# Schematics_MedidorDeTensionAC.net
KiCad netlist of a schematic drawn in EAGLE
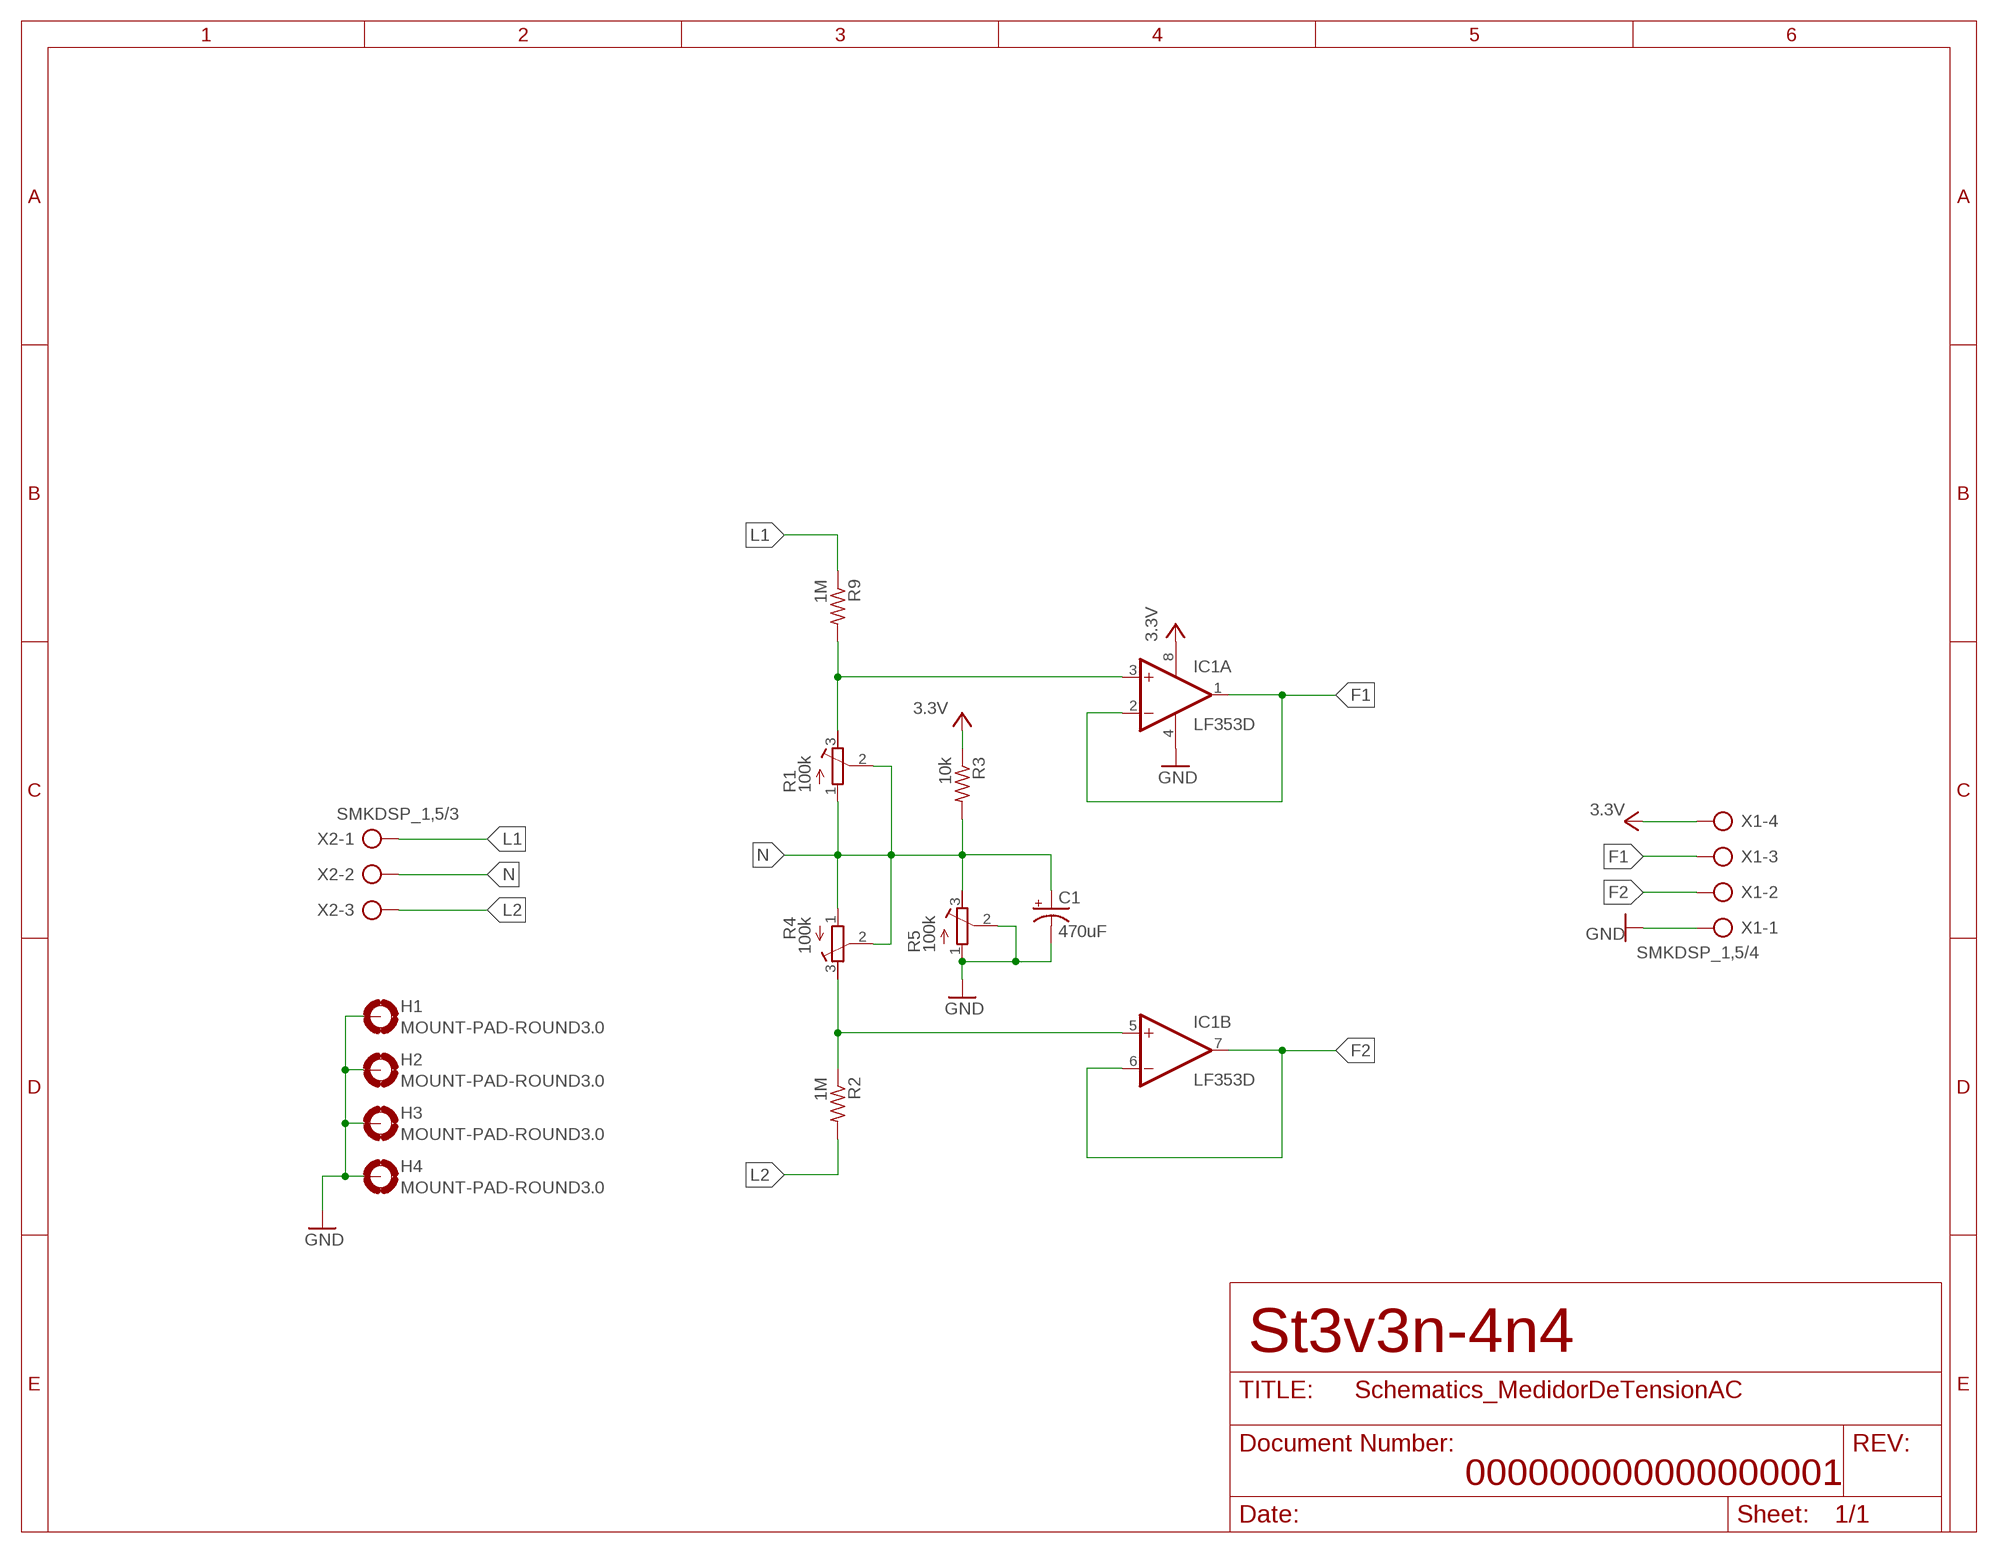
[diagram p0: schematic, sheet 1]

(export (version "E")
  (design (tool "Eeschema 10.0.6"))
  (components
    (comp (ref "C1")
      (value "470uF")
      (footprint "eagle-import:E3,5-8")
      (libsource (lib "eagle-import") (part "CPOL-USE3.5-8"))
    )
    (comp (ref "H1")
      (value "MOUNT-PAD-ROUND3.0")
      (footprint "eagle-import:3,0-PAD")
      (libsource (lib "eagle-import") (part "MOUNT-PAD-ROUND3.0"))
    )
    (comp (ref "H2")
      (value "MOUNT-PAD-ROUND3.0")
      (footprint "eagle-import:3,0-PAD")
      (libsource (lib "eagle-import") (part "MOUNT-PAD-ROUND3.0"))
    )
    (comp (ref "H3")
      (value "MOUNT-PAD-ROUND3.0")
      (footprint "eagle-import:3,0-PAD")
      (libsource (lib "eagle-import") (part "MOUNT-PAD-ROUND3.0"))
    )
    (comp (ref "H4")
      (value "MOUNT-PAD-ROUND3.0")
      (footprint "eagle-import:3,0-PAD")
      (libsource (lib "eagle-import") (part "MOUNT-PAD-ROUND3.0"))
    )
    (comp (ref "IC1")
      (value "LF353D")
      (footprint "eagle-import:SO08")
      (fields (field (name "SPICEPREFIX") "J"))
      (libsource (lib "eagle-import") (part "LF353D"))
    )
    (comp (ref "R1")
      (value "100k")
      (footprint "eagle-import:RTRIM64W")
      (libsource (lib "eagle-import") (part "R-TRIMM64W"))
    )
    (comp (ref "R2")
      (value "1M")
      (footprint "eagle-import:0207_10")
      (libsource (lib "eagle-import") (part "R-US_0207/10"))
    )
    (comp (ref "R3")
      (value "10k")
      (footprint "eagle-import:0207_10")
      (libsource (lib "eagle-import") (part "R-US_0207/10"))
    )
    (comp (ref "R4")
      (value "100k")
      (footprint "eagle-import:RTRIM64W")
      (libsource (lib "eagle-import") (part "R-TRIMM64W"))
    )
    (comp (ref "R5")
      (value "100k")
      (footprint "eagle-import:RTRIM64W")
      (libsource (lib "eagle-import") (part "R-TRIMM64W"))
    )
    (comp (ref "R9")
      (value "1M")
      (footprint "eagle-import:0207_10")
      (libsource (lib "eagle-import") (part "R-US_0207/10"))
    )
    (comp (ref "X1")
      (value "SMKDSP_1,5/4")
      (footprint "eagle-import:SMKDSP_1,5_4")
      (fields (field (name "MF") "FARNELL") (field (name "MPN") "1733596"))
      (libsource (lib "eagle-import") (part "SMKDSP_1,5/4"))
    )
    (comp (ref "X2")
      (value "SMKDSP_1,5/3")
      (footprint "eagle-import:SMKDSP_1,5_3")
      (fields (field (name "MF") "FARNELL") (field (name "MPN") "1733583"))
      (libsource (lib "eagle-import") (part "SMKDSP_1,5/3"))
    )
  )
  (nets
    (net (code "1") (name "3.3V") (class "Default")
      (node (ref "IC1") (pin "8") (pinfunction "V+_8") (pintype "power_in"))
      (node (ref "R3") (pin "1") (pinfunction "1_1") (pintype "passive"))
      (node (ref "X1") (pin "4") (pinfunction "KL_4") (pintype "passive"))
    )
    (net (code "2") (name "F1") (class "Default")
      (node (ref "IC1") (pin "1") (pinfunction "OUT_1") (pintype "output"))
      (node (ref "IC1") (pin "2") (pinfunction "-IN_2") (pintype "input"))
      (node (ref "X1") (pin "3") (pinfunction "KL_3") (pintype "passive"))
    )
    (net (code "3") (name "F2") (class "Default")
      (node (ref "IC1") (pin "6") (pinfunction "-IN_6") (pintype "input"))
      (node (ref "IC1") (pin "7") (pinfunction "OUT_7") (pintype "output"))
      (node (ref "X1") (pin "2") (pinfunction "KL_2") (pintype "passive"))
    )
    (net (code "4") (name "GND") (class "Default")
      (node (ref "C1") (pin "-") (pinfunction "-_-") (pintype "passive"))
      (node (ref "H1") (pin "B3,0") (pinfunction "MOUNT_B3,0") (pintype "passive"))
      (node (ref "H2") (pin "B3,0") (pinfunction "MOUNT_B3,0") (pintype "passive"))
      (node (ref "H3") (pin "B3,0") (pinfunction "MOUNT_B3,0") (pintype "passive"))
      (node (ref "H4") (pin "B3,0") (pinfunction "MOUNT_B3,0") (pintype "passive"))
      (node (ref "IC1") (pin "4") (pinfunction "V-_4") (pintype "power_in"))
      (node (ref "R5") (pin "1") (pinfunction "A_1") (pintype "passive"))
      (node (ref "R5") (pin "2") (pinfunction "S_2") (pintype "passive"))
      (node (ref "X1") (pin "1") (pinfunction "KL_1") (pintype "passive"))
    )
    (net (code "5") (name "L1") (class "Default")
      (node (ref "R9") (pin "1") (pinfunction "1_1") (pintype "passive"))
      (node (ref "X2") (pin "1") (pinfunction "KL_1") (pintype "passive"))
    )
    (net (code "6") (name "L2") (class "Default")
      (node (ref "R2") (pin "2") (pinfunction "2_2") (pintype "passive"))
      (node (ref "X2") (pin "3") (pinfunction "KL_3") (pintype "passive"))
    )
    (net (code "7") (name "N") (class "Default")
      (node (ref "C1") (pin "+") (pinfunction "+_+") (pintype "passive"))
      (node (ref "R1") (pin "1") (pinfunction "A_1") (pintype "passive"))
      (node (ref "R1") (pin "2") (pinfunction "S_2") (pintype "passive"))
      (node (ref "R3") (pin "2") (pinfunction "2_2") (pintype "passive"))
      (node (ref "R4") (pin "1") (pinfunction "A_1") (pintype "passive"))
      (node (ref "R4") (pin "2") (pinfunction "S_2") (pintype "passive"))
      (node (ref "R5") (pin "3") (pinfunction "E_3") (pintype "passive"))
      (node (ref "X2") (pin "2") (pinfunction "KL_2") (pintype "passive"))
    )
    (net (code "8") (name "Net-(IC1A-+IN)") (class "Default")
      (node (ref "IC1") (pin "3") (pinfunction "+IN_3") (pintype "input"))
      (node (ref "R1") (pin "3") (pinfunction "E_3") (pintype "passive"))
      (node (ref "R9") (pin "2") (pinfunction "2_2") (pintype "passive"))
    )
    (net (code "9") (name "Net-(IC1B-+IN)") (class "Default")
      (node (ref "IC1") (pin "5") (pinfunction "+IN_5") (pintype "input"))
      (node (ref "R2") (pin "1") (pinfunction "1_1") (pintype "passive"))
      (node (ref "R4") (pin "3") (pinfunction "E_3") (pintype "passive"))
    )
  )
)
